# config-top.net
KiCad netlist of a schematic drawn in Altium Designer
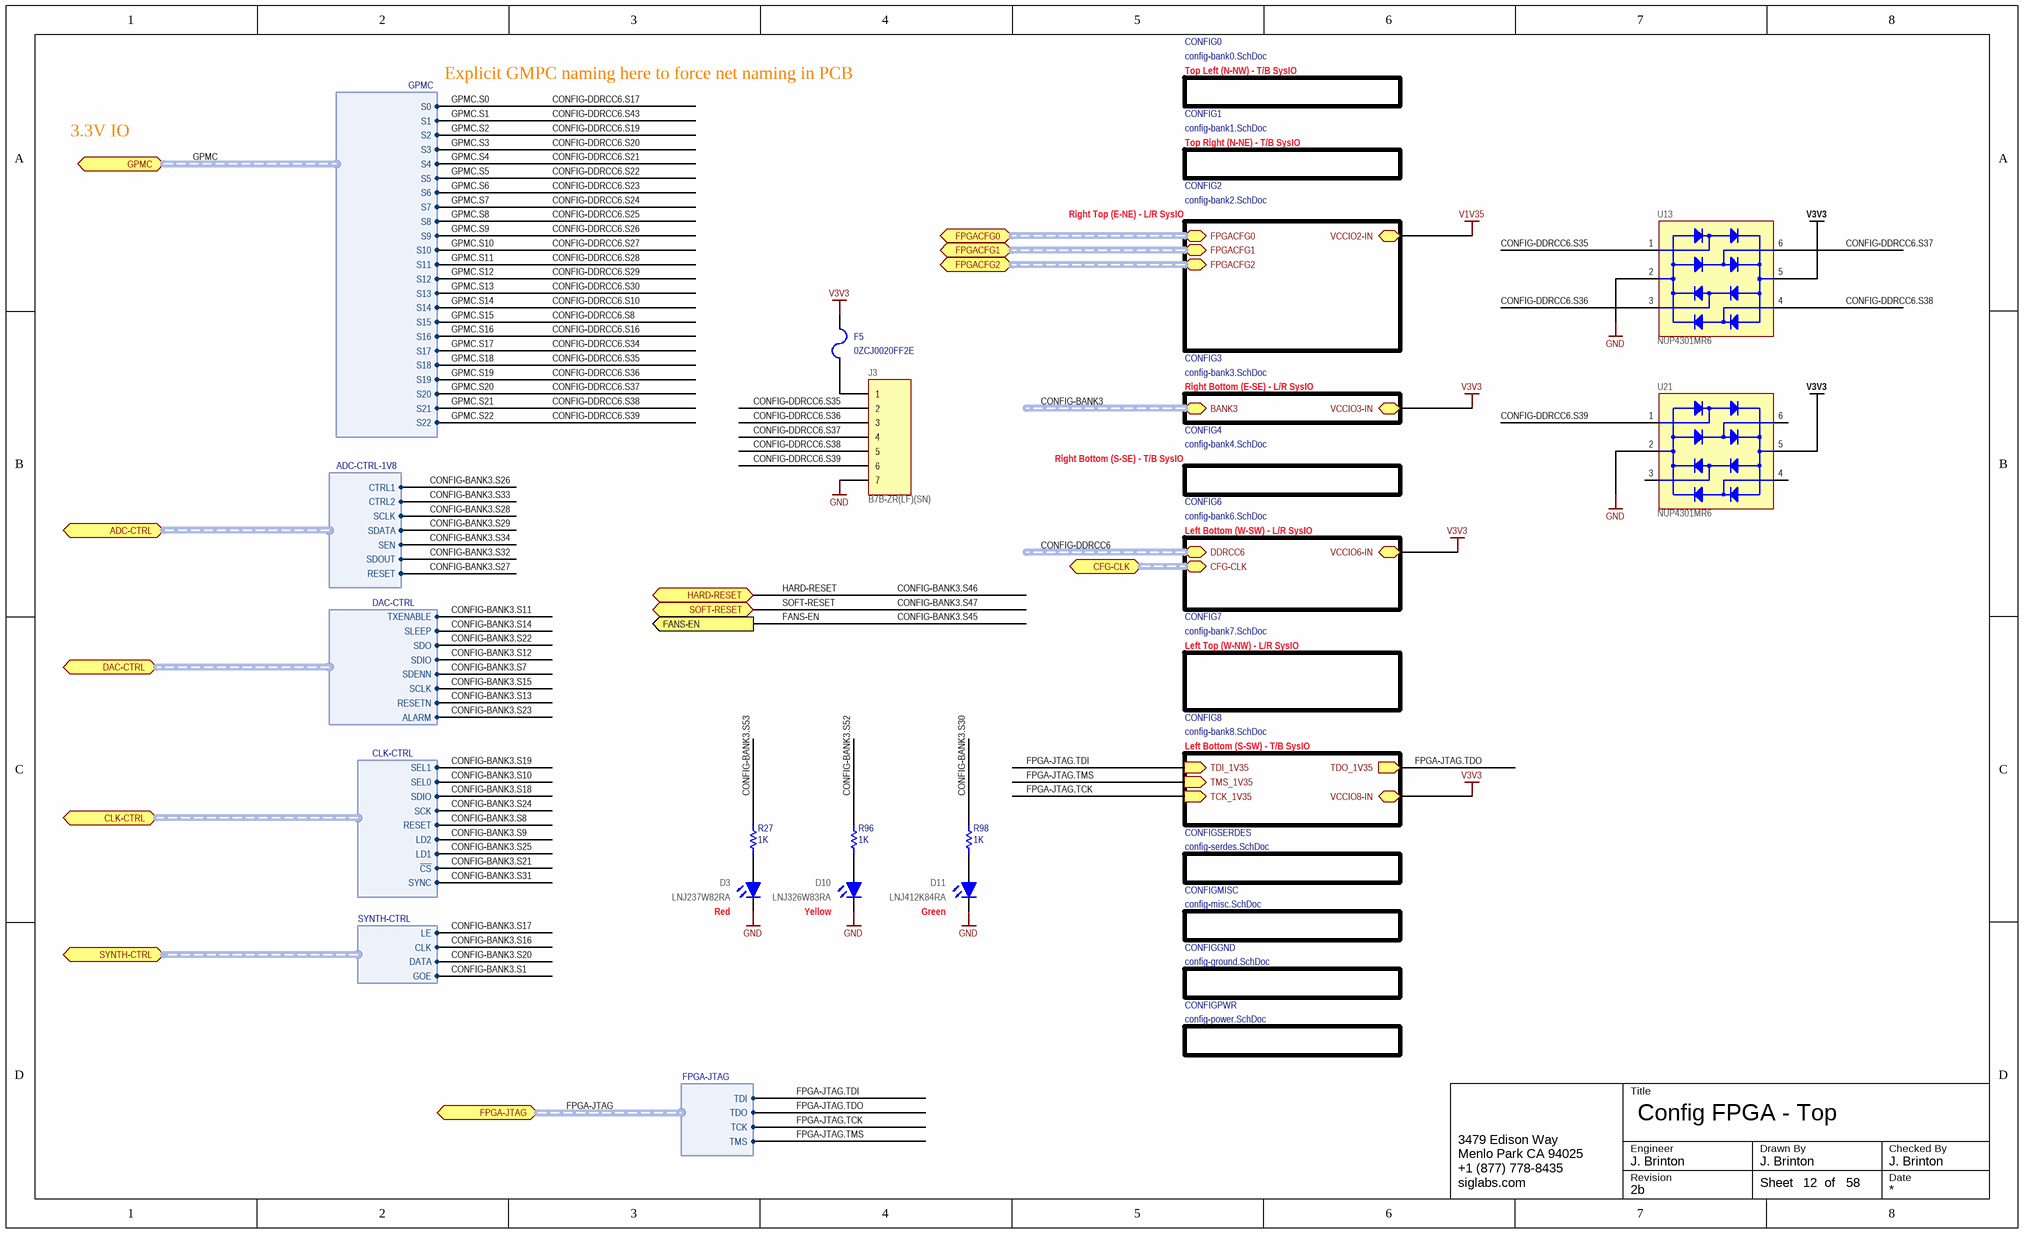
[diagram p0: config-top.SchDoc]

(export (version "E")
  (design (tool "Eeschema 10.0.6"))
  (components
    (comp (ref "D3")
      (value "LNJ237W82RA")
      (footprint "0603_LED")
      (description "LED, SMT 0603, Color Red, 5mA, 1.85V")
      (fields (field (name "MANUFACTURER") "Panasonic"))
      (libsource (lib "generic") (part "LED0603RD"))
    )
    (comp (ref "D10")
      (value "LNJ326W83RA")
      (footprint "0603_LED")
      (description "LED, SMT 0603, Color Green, 10mA, 2.05V")
      (fields (field (name "MANUFACTURER") "Panasonic"))
      (libsource (lib "generic") (part "LED0603GR"))
    )
    (comp (ref "D11")
      (value "LNJ412K84RA")
      (footprint "0603_LED")
      (description "LED, SMT 0603, Color Yellow, 10mA, 2.05V")
      (fields (field (name "MANUFACTURER") "Panasonic"))
      (libsource (lib "generic") (part "LED0603Y"))
    )
    (comp (ref "F5")
      (value "0ZCJ0020FF2E")
      (footprint "generic:1206")
      (description "PTC Resettable Fuse, 0.2A, 30V, SMD 1206")
      (fields (field (name "MANUFACTURER") "Bell Fuse"))
      (libsource (lib "bel-fuse") (part "0ZCJ0020FF2E"))
    )
    (comp (ref "J3")
      (value "B7B-ZR(LF)(SN)")
      (footprint "jst:B7B-ZR")
      (description "Through-hole Shrouded Header 7-Position")
      (fields (field (name "MANUFACTURER") "JST"))
      (libsource (lib "jst") (part "B7B-ZR(LF)(SN)"))
    )
    (comp (ref "R27")
      (value "1K")
      (footprint "generic:0402")
      (description "Thick Film Resistor 1k ±1% 0402")
      (fields (field (name "MANUFACTURER") "Yageo") (field (name "TOLERANCE") "±1%"))
      (libsource (lib "Graviton") (part "RES 0402"))
    )
    (comp (ref "R96")
      (value "1K")
      (footprint "generic:0402")
      (description "Thick Film Resistor 1k ±1% 0402")
      (fields (field (name "MANUFACTURER") "Yageo") (field (name "TOLERANCE") "±1%"))
      (libsource (lib "Graviton") (part "RES 0402"))
    )
    (comp (ref "R98")
      (value "1K")
      (footprint "generic:0402")
      (description "Thick Film Resistor 1k ±1% 0402")
      (fields (field (name "MANUFACTURER") "Yageo") (field (name "TOLERANCE") "±1%"))
      (libsource (lib "Graviton") (part "RES 0402"))
    )
    (comp (ref "U13")
      (value "NUP4301MR6")
      (footprint "generic:SOT23-6")
      (description "4-Lane TVS Diode Array")
      (fields (field (name "MANUFACTURER") "On Semiconductor"))
      (libsource (lib "on_semi") (part "NUP4301MR6"))
    )
    (comp (ref "U21")
      (value "NUP4301MR6")
      (footprint "generic:SOT23-6")
      (description "4-Lane TVS Diode Array")
      (fields (field (name "MANUFACTURER") "On Semiconductor"))
      (libsource (lib "on_semi") (part "NUP4301MR6"))
    )
  )
  (nets
    (net (code "38") (name "/CONFIG-BANK3.S30") (class "Default")
      (node (ref "R98") (pin "2") (pinfunction "2_2") (pintype "passive"))
    )
    (net (code "46") (name "/CONFIG-BANK3.S52") (class "Default")
      (node (ref "R96") (pin "2") (pinfunction "2_2") (pintype "passive"))
    )
    (net (code "47") (name "/CONFIG-BANK3.S53") (class "Default")
      (node (ref "R27") (pin "2") (pinfunction "2_2") (pintype "passive"))
    )
    (net (code "65") (name "/CONFIG-DDRCC6.S35") (class "Default")
      (node (ref "J3") (pin "2") (pinfunction "2_2") (pintype "passive"))
      (node (ref "U13") (pin "1") (pinfunction "A_1") (pintype "passive"))
    )
    (net (code "66") (name "/CONFIG-DDRCC6.S36") (class "Default")
      (node (ref "J3") (pin "3") (pinfunction "3_3") (pintype "passive"))
      (node (ref "U13") (pin "3") (pinfunction "B_3") (pintype "passive"))
    )
    (net (code "67") (name "/CONFIG-DDRCC6.S37") (class "Default")
      (node (ref "J3") (pin "4") (pinfunction "4_4") (pintype "passive"))
      (node (ref "U13") (pin "6") (pinfunction "D_6") (pintype "passive"))
    )
    (net (code "68") (name "/CONFIG-DDRCC6.S38") (class "Default")
      (node (ref "J3") (pin "5") (pinfunction "5_5") (pintype "passive"))
      (node (ref "U13") (pin "4") (pinfunction "C_4") (pintype "passive"))
    )
    (net (code "69") (name "/CONFIG-DDRCC6.S39") (class "Default")
      (node (ref "J3") (pin "6") (pinfunction "6_6") (pintype "passive"))
      (node (ref "U21") (pin "1") (pinfunction "A_1") (pintype "passive"))
    )
    (net (code "86") (name "GND") (class "Default")
      (node (ref "D10") (pin "2") (pinfunction "K_2") (pintype "passive"))
      (node (ref "D11") (pin "2") (pinfunction "K_2") (pintype "passive"))
      (node (ref "D3") (pin "2") (pinfunction "K_2") (pintype "passive"))
      (node (ref "J3") (pin "7") (pinfunction "7_7") (pintype "passive"))
      (node (ref "U13") (pin "2") (pinfunction "VN_2") (pintype "passive"))
      (node (ref "U21") (pin "2") (pinfunction "VN_2") (pintype "passive"))
    )
    (net (code "87") (name "Net-(D3-A)") (class "Default")
      (node (ref "D3") (pin "1") (pinfunction "A_1") (pintype "passive"))
      (node (ref "R27") (pin "1") (pinfunction "1_1") (pintype "passive"))
    )
    (net (code "88") (name "Net-(D10-A)") (class "Default")
      (node (ref "D10") (pin "1") (pinfunction "A_1") (pintype "passive"))
      (node (ref "R96") (pin "1") (pinfunction "1_1") (pintype "passive"))
    )
    (net (code "89") (name "Net-(D11-A)") (class "Default")
      (node (ref "D11") (pin "1") (pinfunction "A_1") (pintype "passive"))
      (node (ref "R98") (pin "1") (pinfunction "1_1") (pintype "passive"))
    )
    (net (code "90") (name "Net-(F5-Pad1)") (class "Default")
      (node (ref "F5") (pin "1") (pinfunction "1_1") (pintype "passive"))
      (node (ref "J3") (pin "1") (pinfunction "1_1") (pintype "passive"))
    )
    (net (code "92") (name "V3V3") (class "Default")
      (node (ref "F5") (pin "2") (pinfunction "2_2") (pintype "passive"))
      (node (ref "U13") (pin "5") (pinfunction "VP_5") (pintype "passive"))
      (node (ref "U21") (pin "5") (pinfunction "VP_5") (pintype "passive"))
    )
    (net (code "93") (name "unconnected-(U21-B-Pad3)") (class "Default")
      (node (ref "U21") (pin "3") (pinfunction "B_3") (pintype "passive"))
    )
    (net (code "94") (name "unconnected-(U21-C-Pad4)") (class "Default")
      (node (ref "U21") (pin "4") (pinfunction "C_4") (pintype "passive"))
    )
    (net (code "95") (name "unconnected-(U21-D-Pad6)") (class "Default")
      (node (ref "U21") (pin "6") (pinfunction "D_6") (pintype "passive"))
    )
  )
)
